# schemantic.net
KiCad netlist of a schematic drawn in EAGLE
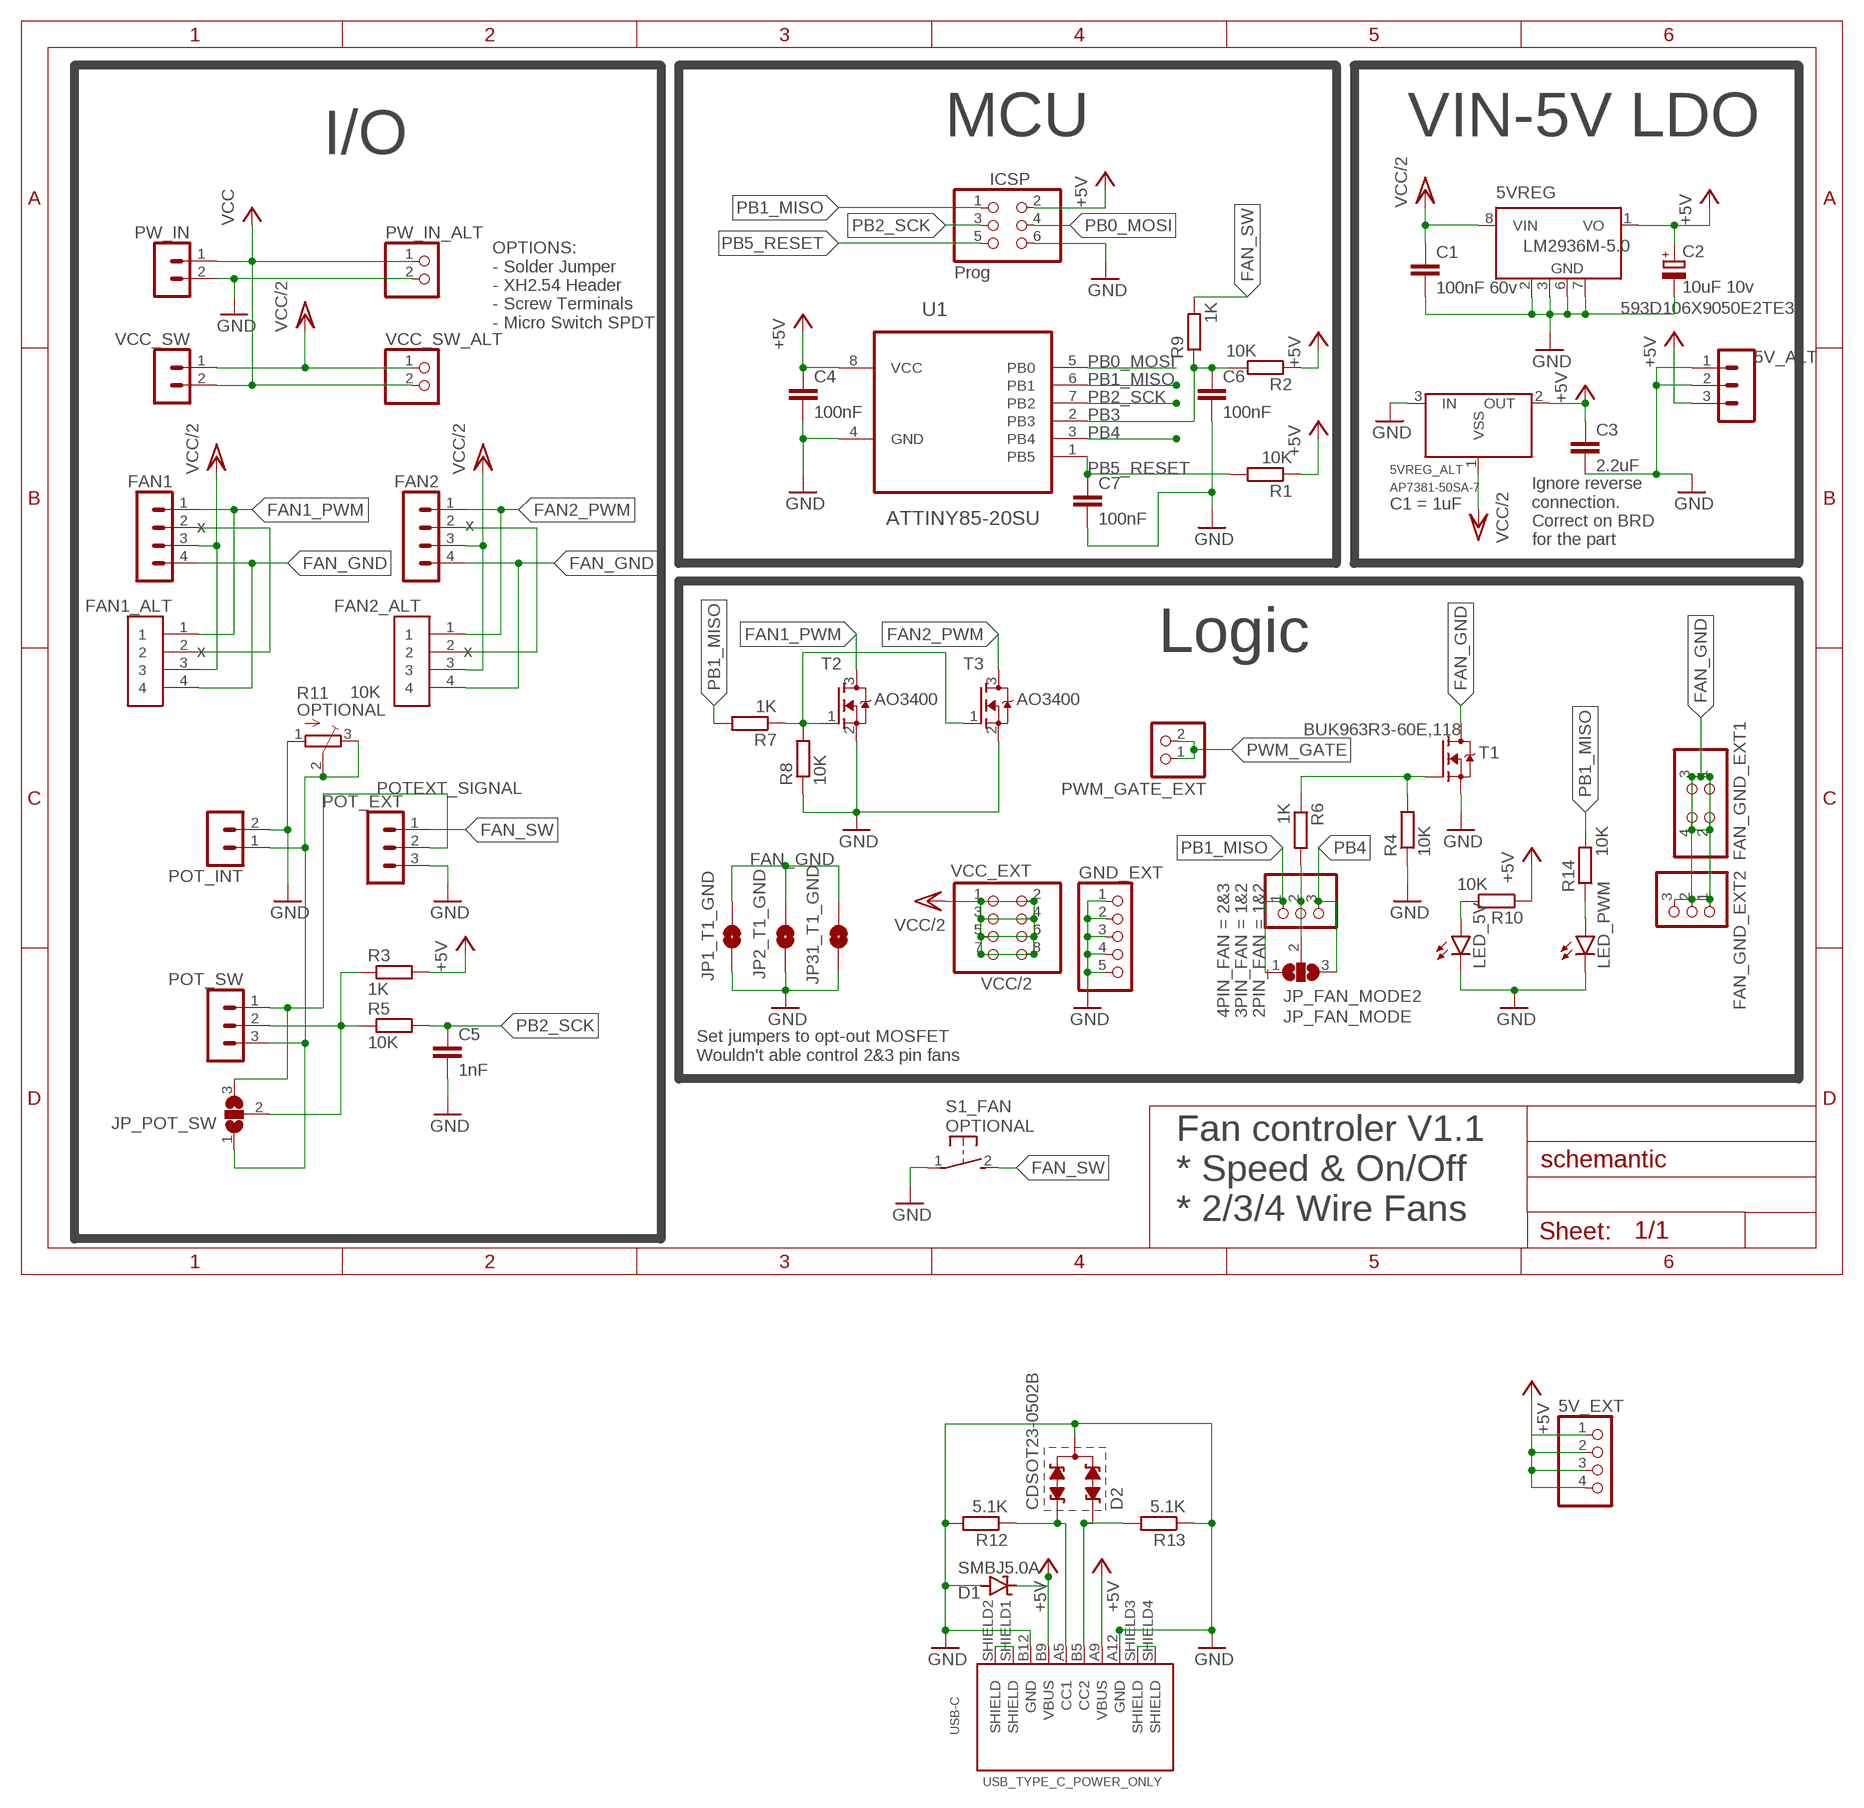
[diagram p0: schematic, sheet 1]

(export (version "E")
  (design (tool "Eeschema 10.0.6"))
  (components
    (comp (ref "5VREG")
      (value "LM2936M-5.0")
      (footprint "eagle-import:SO08")
      (fields
        (field (name "MF") "NATIONAL SEMICONDUCTOR")
        (field (name "MPN") "LM2936M-5.0/NOPB")
        (field (name "MPN_1") "LM2936HVMA-5.0/NOPB")
      )
      (libsource (lib "eagle-import") (part "LM2936M?-5.0"))
    )
    (comp (ref "5VREG_ALT")
      (value "AP7381-50SA-7")
      (footprint "eagle-import:XC6206_SOT-23")
      (fields (field (name "C1") "1uF"))
      (libsource (lib "eagle-import") (part "XC6206SOT-23"))
    )
    (comp (ref "5V_ALT")
      (value "B3B-XH-2")
      (footprint "eagle-import:B3B-XH-A")
      (libsource (lib "eagle-import") (part "B3B-XH-2"))
    )
    (comp (ref "5V_EXT")
      (value "PINHD-1X4")
      (footprint "eagle-import:1X04")
      (libsource (lib "eagle-import") (part "PINHD-1X4"))
    )
    (comp (ref "C1")
      (value "100nF 60v")
      (footprint "eagle-import:C1206")
      (libsource (lib "eagle-import") (part "C-EUC1206"))
    )
    (comp (ref "C2")
      (value "10uF 10v")
      (footprint "eagle-import:SMC_E")
      (fields (field (name "MODEL") "593D106X9050E2TE3"))
      (libsource (lib "eagle-import") (part "CPOL-EUSMCE"))
    )
    (comp (ref "C3")
      (value "2.2uF")
      (footprint "eagle-import:C0603")
      (libsource (lib "eagle-import") (part "C-EUC0603"))
    )
    (comp (ref "C4")
      (value "100nF")
      (footprint "eagle-import:C0603")
      (libsource (lib "eagle-import") (part "C-EUC0603"))
    )
    (comp (ref "C5")
      (value "1nF")
      (footprint "eagle-import:C0603")
      (libsource (lib "eagle-import") (part "C-EUC0603"))
    )
    (comp (ref "C6")
      (value "100nF")
      (footprint "eagle-import:C0603")
      (libsource (lib "eagle-import") (part "C-EUC0603"))
    )
    (comp (ref "C7")
      (value "100nF")
      (footprint "eagle-import:C0603")
      (libsource (lib "eagle-import") (part "C-EUC0603"))
    )
    (comp (ref "D1")
      (value "SMBJ5.0A")
      (footprint "eagle-import:SMBJ")
      (libsource (lib "eagle-import") (part "SUPPRESSOR-SMBJ"))
    )
    (comp (ref "D2")
      (value "CDSOT23-0502B")
      (footprint "eagle-import:SOT23")
      (libsource (lib "eagle-import") (part "CDSOT23-0502B"))
    )
    (comp (ref "FAN1")
      (value "FAN1")
      (footprint "eagle-import:B4P-VH")
      (libsource (lib "eagle-import") (part "B4P-VH"))
    )
    (comp (ref "FAN1_ALT")
      (value "1X4-BIG")
      (footprint "eagle-import:1X04-BIG")
      (libsource (lib "eagle-import") (part "1X4-BIG"))
    )
    (comp (ref "FAN2")
      (value "FAN1")
      (footprint "eagle-import:B4P-VH")
      (libsource (lib "eagle-import") (part "B4P-VH"))
    )
    (comp (ref "FAN2_ALT")
      (value "1X4-BIG")
      (footprint "eagle-import:1X04-BIG")
      (libsource (lib "eagle-import") (part "1X4-BIG"))
    )
    (comp (ref "FAN_GND_EXT1")
      (value "PINHD-2X2")
      (footprint "eagle-import:2X02")
      (libsource (lib "eagle-import") (part "PINHD-2X2"))
    )
    (comp (ref "FAN_GND_EXT2")
      (value "PINHD-1X3")
      (footprint "eagle-import:1X03")
      (libsource (lib "eagle-import") (part "pinhead_PINHD-1X3"))
    )
    (comp (ref "GND_EXT")
      (value "PINHD-1X5")
      (footprint "eagle-import:1X05")
      (libsource (lib "eagle-import") (part "PINHD-1X5"))
    )
    (comp (ref "ICSP")
      (value "Prog")
      (footprint "eagle-import:2X03")
      (libsource (lib "eagle-import") (part "PINHD-2X3"))
    )
    (comp (ref "JP1_T1_GND")
      (value "JUMPER-SMT_2_NO_NO-SILK")
      (footprint "eagle-import:SMT-JUMPER_2_NO_NO-SILK")
      (libsource (lib "eagle-import") (part "JUMPER-SMT_2_NO_NO-SILK"))
    )
    (comp (ref "JP2_T1_GND")
      (value "JUMPER-SMT_2_NO_NO-SILK")
      (footprint "eagle-import:SMT-JUMPER_2_NO_NO-SILK")
      (libsource (lib "eagle-import") (part "JUMPER-SMT_2_NO_NO-SILK"))
    )
    (comp (ref "JP31_T1_GND")
      (value "JUMPER-SMT_2_NO_NO-SILK")
      (footprint "eagle-import:SMT-JUMPER_2_NO_NO-SILK")
      (libsource (lib "eagle-import") (part "JUMPER-SMT_2_NO_NO-SILK"))
    )
    (comp (ref "JP_FAN_MODE")
      (value "DC_COM_PWM")
      (footprint "eagle-import:SJ_2")
      (libsource (lib "eagle-import") (part "SJ2W"))
    )
    (comp (ref "JP_FAN_MODE2")
      (value "PINHD-1X3")
      (footprint "eagle-import:1X03")
      (fields (field (name "2PIN_FAN") "1&2") (field (name "3PIN_FAN") "1&2") (field (name "4PIN_FAN") "2&3"))
      (libsource (lib "eagle-import") (part "PINHD-1X3"))
    )
    (comp (ref "JP_POT_SW")
      (value "SJ2W")
      (footprint "eagle-import:SJ_2")
      (libsource (lib "eagle-import") (part "SJ2W"))
    )
    (comp (ref "LED_5V")
      (value "LEDCHIPLED_0805")
      (footprint "eagle-import:CHIPLED_0805")
      (libsource (lib "eagle-import") (part "LEDCHIPLED_0805"))
    )
    (comp (ref "LED_PWM")
      (value "LEDCHIPLED_0805")
      (footprint "eagle-import:CHIPLED_0805")
      (libsource (lib "eagle-import") (part "LEDCHIPLED_0805"))
    )
    (comp (ref "POT_EXT")
      (value "POT_EXT")
      (footprint "eagle-import:B3B-XH-A")
      (libsource (lib "eagle-import") (part "B3B-XH-2"))
    )
    (comp (ref "POT_INT")
      (value "POT_INT")
      (footprint "eagle-import:B2B-XH-A")
      (libsource (lib "eagle-import") (part "B2B-XH-2"))
    )
    (comp (ref "POT_SW")
      (value "POT_SW")
      (footprint "eagle-import:B3B-XH-A")
      (libsource (lib "eagle-import") (part "B3B-XH-2"))
    )
    (comp (ref "PWM_GATE_EXT")
      (value "PINHD-1X2")
      (footprint "eagle-import:1X02")
      (libsource (lib "eagle-import") (part "PINHD-1X2"))
    )
    (comp (ref "PW_IN")
      (value "Power In")
      (footprint "eagle-import:B2P-VH")
      (libsource (lib "eagle-import") (part "B2P-VH"))
    )
    (comp (ref "PW_IN_ALT")
      (value "PINHD-1X2")
      (footprint "eagle-import:1X02")
      (libsource (lib "eagle-import") (part "pinhead_325_PINHD-1X2"))
    )
    (comp (ref "R1")
      (value "10K")
      (footprint "eagle-import:R0603")
      (fields (field (name "SPICEPREFIX") "R"))
      (libsource (lib "eagle-import") (part "R-EU_R0603"))
    )
    (comp (ref "R2")
      (value "10K")
      (footprint "eagle-import:R0603")
      (fields (field (name "SPICEPREFIX") "R"))
      (libsource (lib "eagle-import") (part "R-EU_R0603"))
    )
    (comp (ref "R3")
      (value "1K")
      (footprint "eagle-import:R0603")
      (libsource (lib "eagle-import") (part "R-EU_R0603"))
    )
    (comp (ref "R4")
      (value "10K")
      (footprint "eagle-import:R0603")
      (fields (field (name "SPICEPREFIX") "R"))
      (libsource (lib "eagle-import") (part "R-EU_R0603"))
    )
    (comp (ref "R5")
      (value "10K")
      (footprint "eagle-import:R0603")
      (libsource (lib "eagle-import") (part "R-EU_R0603"))
    )
    (comp (ref "R6")
      (value "1K")
      (footprint "eagle-import:R0603")
      (fields (field (name "SPICEPREFIX") "R"))
      (libsource (lib "eagle-import") (part "R-EU_R0603"))
    )
    (comp (ref "R7")
      (value "1K")
      (footprint "eagle-import:R0603")
      (fields (field (name "SPICEPREFIX") "R"))
      (libsource (lib "eagle-import") (part "R-EU_R0603"))
    )
    (comp (ref "R8")
      (value "10K")
      (footprint "eagle-import:R0603")
      (fields (field (name "SPICEPREFIX") "R"))
      (libsource (lib "eagle-import") (part "R-EU_R0603"))
    )
    (comp (ref "R9")
      (value "1K")
      (footprint "eagle-import:R0603")
      (libsource (lib "eagle-import") (part "R-EU_R0603"))
    )
    (comp (ref "R10")
      (value "10K")
      (footprint "eagle-import:R0603")
      (libsource (lib "eagle-import") (part "R-EU_R0603"))
    )
    (comp (ref "R11")
      (value "10K")
      (footprint "eagle-import:3223W")
      (libsource (lib "eagle-import") (part "TRIM_EU-3223W"))
    )
    (comp (ref "R12")
      (value "5.1K")
      (footprint "eagle-import:R0603")
      (libsource (lib "eagle-import") (part "R-EU_R0603"))
    )
    (comp (ref "R13")
      (value "5.1K")
      (footprint "eagle-import:R0603")
      (libsource (lib "eagle-import") (part "R-EU_R0603"))
    )
    (comp (ref "R14")
      (value "10K")
      (footprint "eagle-import:R0603")
      (libsource (lib "eagle-import") (part "R-EU_R0603"))
    )
    (comp (ref "S1_FAN")
      (value "DTSM-3")
      (footprint "eagle-import:DTSM-3")
      (libsource (lib "eagle-import") (part "DTSM-3"))
    )
    (comp (ref "T1")
      (value "BUK963R3-60E,118")
      (footprint "eagle-import:D2PAK_TO263")
      (libsource (lib "eagle-import") (part "MOSFET-N-D2PAK"))
    )
    (comp (ref "T2")
      (value "AO3400")
      (footprint "eagle-import:SOT23")
      (fields (field (name "SPICEPREFIX") "J"))
      (libsource (lib "eagle-import") (part "MOSFET-NREFLOW"))
    )
    (comp (ref "T3")
      (value "AO3400")
      (footprint "eagle-import:SOT23")
      (fields (field (name "SPICEPREFIX") "J"))
      (libsource (lib "eagle-import") (part "MOSFET-NREFLOW"))
    )
    (comp (ref "U1")
      (value "ATTINY85-20SU")
      (footprint "eagle-import:SOIC127P798X216-8N")
      (libsource (lib "eagle-import") (part "ATTINY85-20SU"))
    )
    (comp (ref "USB-C")
      (value "USB_TYPE_C_POWER_ONLY")
      (footprint "eagle-import:USB_TYPE_C_POWER_ONLY")
      (libsource (lib "eagle-import") (part "USB_TYPE_C_POWER_ONLY"))
    )
    (comp (ref "VCC_EXT")
      (value "PINHD-2X4")
      (footprint "eagle-import:2X04")
      (libsource (lib "eagle-import") (part "PINHD-2X4"))
    )
    (comp (ref "VCC_SW")
      (value "Power SW")
      (footprint "eagle-import:B2P-VH")
      (libsource (lib "eagle-import") (part "B2P-VH"))
    )
    (comp (ref "VCC_SW_ALT")
      (value "PINHD-1X2")
      (footprint "eagle-import:1X02")
      (libsource (lib "eagle-import") (part "pinhead_325_PINHD-1X2"))
    )
  )
  (nets
    (net (code "1") (name "+5V") (class "Default")
      (node (ref "5VREG") (pin "1") (pinfunction "VO_1") (pintype "passive"))
      (node (ref "5VREG_ALT") (pin "2") (pinfunction "OUT_2") (pintype "bidirectional"))
      (node (ref "5V_ALT") (pin "3") (pinfunction "3_3") (pintype "passive"))
      (node (ref "5V_EXT") (pin "1") (pinfunction "1_1") (pintype "passive"))
      (node (ref "5V_EXT") (pin "2") (pinfunction "2_2") (pintype "passive"))
      (node (ref "5V_EXT") (pin "3") (pinfunction "3_3") (pintype "passive"))
      (node (ref "5V_EXT") (pin "4") (pinfunction "4_4") (pintype "passive"))
      (node (ref "C2") (pin "+") (pinfunction "+_+") (pintype "passive"))
      (node (ref "C3") (pin "1") (pinfunction "1_1") (pintype "passive"))
      (node (ref "C4") (pin "1") (pinfunction "1_1") (pintype "passive"))
      (node (ref "D1") (pin "C") (pinfunction "C_C") (pintype "passive"))
      (node (ref "ICSP") (pin "2") (pinfunction "2_2") (pintype "passive"))
      (node (ref "R1") (pin "1") (pinfunction "1_1") (pintype "passive"))
      (node (ref "R10") (pin "1") (pinfunction "1_1") (pintype "passive"))
      (node (ref "R2") (pin "1") (pinfunction "1_1") (pintype "passive"))
      (node (ref "R3") (pin "2") (pinfunction "2_2") (pintype "passive"))
      (node (ref "U1") (pin "8") (pinfunction "VCC_8") (pintype "power_in"))
      (node (ref "USB-C") (pin "A9") (pinfunction "VBUS_A9") (pintype "power_in"))
      (node (ref "USB-C") (pin "B9") (pinfunction "VBUS_B9") (pintype "power_in"))
    )
    (net (code "2") (name "/PB3") (class "Default")
      (node (ref "C6") (pin "1") (pinfunction "1_1") (pintype "passive"))
      (node (ref "R2") (pin "2") (pinfunction "2_2") (pintype "passive"))
      (node (ref "R9") (pin "1") (pinfunction "1_1") (pintype "passive"))
      (node (ref "U1") (pin "2") (pinfunction "PB3_2") (pintype "bidirectional"))
    )
    (net (code "3") (name "/POTEXT_SIGNAL") (class "Default")
      (node (ref "JP_POT_SW") (pin "3") (pinfunction "3_3") (pintype "passive"))
      (node (ref "POT_EXT") (pin "2") (pinfunction "2_2") (pintype "passive"))
      (node (ref "POT_SW") (pin "1") (pinfunction "1_1") (pintype "passive"))
    )
    (net (code "4") (name "FAN1_PWM") (class "Default")
      (node (ref "FAN1") (pin "1") (pinfunction "1_1") (pintype "passive"))
      (node (ref "FAN1_ALT") (pin "1") (pinfunction "1_1") (pintype "bidirectional"))
      (node (ref "T2") (pin "3") (pinfunction "D_3") (pintype "bidirectional"))
    )
    (net (code "5") (name "FAN2_PWM") (class "Default")
      (node (ref "FAN2") (pin "1") (pinfunction "1_1") (pintype "passive"))
      (node (ref "FAN2_ALT") (pin "1") (pinfunction "1_1") (pintype "bidirectional"))
      (node (ref "T3") (pin "3") (pinfunction "D_3") (pintype "bidirectional"))
    )
    (net (code "6") (name "FAN_GND") (class "Default")
      (node (ref "FAN1") (pin "4") (pinfunction "4_4") (pintype "passive"))
      (node (ref "FAN1_ALT") (pin "4") (pinfunction "4_4") (pintype "bidirectional"))
      (node (ref "FAN2") (pin "4") (pinfunction "4_4") (pintype "passive"))
      (node (ref "FAN2_ALT") (pin "4") (pinfunction "4_4") (pintype "bidirectional"))
      (node (ref "FAN_GND_EXT1") (pin "1") (pinfunction "1_1") (pintype "passive"))
      (node (ref "FAN_GND_EXT1") (pin "2") (pinfunction "2_2") (pintype "passive"))
      (node (ref "FAN_GND_EXT1") (pin "3") (pinfunction "3_3") (pintype "passive"))
      (node (ref "FAN_GND_EXT1") (pin "4") (pinfunction "4_4") (pintype "passive"))
      (node (ref "FAN_GND_EXT2") (pin "1") (pinfunction "1_1") (pintype "passive"))
      (node (ref "FAN_GND_EXT2") (pin "2") (pinfunction "2_2") (pintype "passive"))
      (node (ref "FAN_GND_EXT2") (pin "3") (pinfunction "3_3") (pintype "passive"))
      (node (ref "JP1_T1_GND") (pin "2") (pinfunction "2_2") (pintype "passive"))
      (node (ref "JP2_T1_GND") (pin "2") (pinfunction "2_2") (pintype "passive"))
      (node (ref "JP31_T1_GND") (pin "2") (pinfunction "2_2") (pintype "passive"))
      (node (ref "T1") (pin "2") (pinfunction "D_2") (pintype "passive"))
    )
    (net (code "7") (name "FAN_SW") (class "Default")
      (node (ref "POT_EXT") (pin "1") (pinfunction "1_1") (pintype "passive"))
      (node (ref "R9") (pin "2") (pinfunction "2_2") (pintype "passive"))
      (node (ref "S1_FAN") (pin "2") (pinfunction "2_2") (pintype "passive"))
    )
    (net (code "8") (name "GND") (class "Default")
      (node (ref "5VREG") (pin "2") (pinfunction "GND_2") (pintype "passive"))
      (node (ref "5VREG") (pin "3") (pinfunction "GND_3") (pintype "passive"))
      (node (ref "5VREG") (pin "6") (pinfunction "GND_6") (pintype "passive"))
      (node (ref "5VREG") (pin "7") (pinfunction "GND_7") (pintype "passive"))
      (node (ref "5VREG_ALT") (pin "3") (pinfunction "IN_3") (pintype "bidirectional"))
      (node (ref "5V_ALT") (pin "1") (pinfunction "1_1") (pintype "passive"))
      (node (ref "5V_ALT") (pin "2") (pinfunction "2_2") (pintype "passive"))
      (node (ref "C1") (pin "2") (pinfunction "2_2") (pintype "passive"))
      (node (ref "C2") (pin "-") (pinfunction "-_-") (pintype "passive"))
      (node (ref "C3") (pin "2") (pinfunction "2_2") (pintype "passive"))
      (node (ref "C4") (pin "2") (pinfunction "2_2") (pintype "passive"))
      (node (ref "C5") (pin "2") (pinfunction "2_2") (pintype "passive"))
      (node (ref "C6") (pin "2") (pinfunction "2_2") (pintype "passive"))
      (node (ref "C7") (pin "2") (pinfunction "2_2") (pintype "passive"))
      (node (ref "D1") (pin "A") (pinfunction "A_A") (pintype "passive"))
      (node (ref "D2") (pin "3") (pinfunction "3_3") (pintype "passive"))
      (node (ref "GND_EXT") (pin "1") (pinfunction "1_1") (pintype "passive"))
      (node (ref "GND_EXT") (pin "2") (pinfunction "2_2") (pintype "passive"))
      (node (ref "GND_EXT") (pin "3") (pinfunction "3_3") (pintype "passive"))
      (node (ref "GND_EXT") (pin "4") (pinfunction "4_4") (pintype "passive"))
      (node (ref "GND_EXT") (pin "5") (pinfunction "5_5") (pintype "passive"))
      (node (ref "ICSP") (pin "6") (pinfunction "6_6") (pintype "passive"))
      (node (ref "JP1_T1_GND") (pin "1") (pinfunction "1_1") (pintype "passive"))
      (node (ref "JP2_T1_GND") (pin "1") (pinfunction "1_1") (pintype "passive"))
      (node (ref "JP31_T1_GND") (pin "1") (pinfunction "1_1") (pintype "passive"))
      (node (ref "LED_5V") (pin "C") (pinfunction "C_C") (pintype "passive"))
      (node (ref "LED_PWM") (pin "C") (pinfunction "C_C") (pintype "passive"))
      (node (ref "POT_EXT") (pin "3") (pinfunction "3_3") (pintype "passive"))
      (node (ref "POT_INT") (pin "2") (pinfunction "2_2") (pintype "passive"))
      (node (ref "PW_IN") (pin "2") (pinfunction "2_2") (pintype "passive"))
      (node (ref "PW_IN_ALT") (pin "2") (pinfunction "2_2") (pintype "passive"))
      (node (ref "R11") (pin "1") (pinfunction "A_1") (pintype "passive"))
      (node (ref "R12") (pin "2") (pinfunction "2_2") (pintype "passive"))
      (node (ref "R13") (pin "1") (pinfunction "1_1") (pintype "passive"))
      (node (ref "R4") (pin "1") (pinfunction "1_1") (pintype "passive"))
      (node (ref "R8") (pin "1") (pinfunction "1_1") (pintype "passive"))
      (node (ref "S1_FAN") (pin "1") (pinfunction "1_1") (pintype "passive"))
      (node (ref "T1") (pin "3") (pinfunction "S_3") (pintype "passive"))
      (node (ref "T2") (pin "2") (pinfunction "S_2") (pintype "bidirectional"))
      (node (ref "T3") (pin "2") (pinfunction "S_2") (pintype "bidirectional"))
      (node (ref "U1") (pin "4") (pinfunction "GND_4") (pintype "passive"))
      (node (ref "USB-C") (pin "A12") (pinfunction "GND_A12") (pintype "power_in"))
      (node (ref "USB-C") (pin "B12") (pinfunction "GND_B12") (pintype "power_in"))
    )
    (net (code "9") (name "Net-(FAN1-Pad2)") (class "Default")
      (node (ref "FAN1") (pin "2") (pinfunction "2_2") (pintype "passive"))
      (node (ref "FAN1_ALT") (pin "2") (pinfunction "2_2") (pintype "bidirectional"))
    )
    (net (code "10") (name "Net-(FAN2-Pad2)") (class "Default")
      (node (ref "FAN2") (pin "2") (pinfunction "2_2") (pintype "passive"))
      (node (ref "FAN2_ALT") (pin "2") (pinfunction "2_2") (pintype "bidirectional"))
    )
    (net (code "11") (name "Net-(JP_FAN_MODE-Pad2)") (class "Default")
      (node (ref "JP_FAN_MODE") (pin "2") (pinfunction "2_2") (pintype "passive"))
      (node (ref "JP_FAN_MODE2") (pin "2") (pinfunction "2_2") (pintype "passive"))
      (node (ref "R6") (pin "2") (pinfunction "2_2") (pintype "passive"))
    )
    (net (code "12") (name "Net-(JP_POT_SW-Pad2)") (class "Default")
      (node (ref "JP_POT_SW") (pin "2") (pinfunction "2_2") (pintype "passive"))
      (node (ref "POT_SW") (pin "2") (pinfunction "2_2") (pintype "passive"))
      (node (ref "R3") (pin "1") (pinfunction "1_1") (pintype "passive"))
      (node (ref "R5") (pin "1") (pinfunction "1_1") (pintype "passive"))
    )
    (net (code "13") (name "Net-(LED_5V-PadA)") (class "Default")
      (node (ref "LED_5V") (pin "A") (pinfunction "A_A") (pintype "passive"))
      (node (ref "R10") (pin "2") (pinfunction "2_2") (pintype "passive"))
    )
    (net (code "14") (name "Net-(LED_PWM-PadA)") (class "Default")
      (node (ref "LED_PWM") (pin "A") (pinfunction "A_A") (pintype "passive"))
      (node (ref "R14") (pin "1") (pinfunction "1_1") (pintype "passive"))
    )
    (net (code "15") (name "Net-(R11-E)") (class "Default")
      (node (ref "JP_POT_SW") (pin "1") (pinfunction "1_1") (pintype "passive"))
      (node (ref "POT_INT") (pin "1") (pinfunction "1_1") (pintype "passive"))
      (node (ref "POT_SW") (pin "3") (pinfunction "3_3") (pintype "passive"))
      (node (ref "R11") (pin "2") (pinfunction "S_2") (pintype "passive"))
      (node (ref "R11") (pin "3") (pinfunction "E_3") (pintype "passive"))
    )
    (net (code "16") (name "Net-(T1-G)") (class "Default")
      (node (ref "R4") (pin "2") (pinfunction "2_2") (pintype "passive"))
      (node (ref "R6") (pin "1") (pinfunction "1_1") (pintype "passive"))
      (node (ref "T1") (pin "1") (pinfunction "G_1") (pintype "passive"))
    )
    (net (code "17") (name "Net-(USB-C-CC1)") (class "Default")
      (node (ref "D2") (pin "2") (pinfunction "2_2") (pintype "passive"))
      (node (ref "R12") (pin "1") (pinfunction "1_1") (pintype "passive"))
      (node (ref "USB-C") (pin "A5") (pinfunction "CC1_A5") (pintype "bidirectional"))
    )
    (net (code "18") (name "Net-(USB-C-CC2)") (class "Default")
      (node (ref "D2") (pin "1") (pinfunction "1_1") (pintype "passive"))
      (node (ref "R13") (pin "2") (pinfunction "2_2") (pintype "passive"))
      (node (ref "USB-C") (pin "B5") (pinfunction "CC2_B5") (pintype "bidirectional"))
    )
    (net (code "19") (name "Net-(USB-C-SHIELD-PadSHIELD1)") (class "Default")
      (node (ref "USB-C") (pin "SHIELD1") (pinfunction "SHIELD_SHIELD1") (pintype "power_in"))
      (node (ref "USB-C") (pin "SHIELD2") (pinfunction "SHIELD_SHIELD2") (pintype "power_in"))
    )
    (net (code "20") (name "Net-(USB-C-SHIELD-PadSHIELD3)") (class "Default")
      (node (ref "USB-C") (pin "SHIELD3") (pinfunction "SHIELD_SHIELD3") (pintype "power_in"))
      (node (ref "USB-C") (pin "SHIELD4") (pinfunction "SHIELD_SHIELD4") (pintype "power_in"))
    )
    (net (code "21") (name "PB0_MOSI") (class "Default")
      (node (ref "ICSP") (pin "4") (pinfunction "4_4") (pintype "passive"))
      (node (ref "U1") (pin "5") (pinfunction "PB0_5") (pintype "bidirectional"))
    )
    (net (code "22") (name "PB1_MISO") (class "Default")
      (node (ref "ICSP") (pin "1") (pinfunction "1_1") (pintype "passive"))
      (node (ref "JP_FAN_MODE") (pin "1") (pinfunction "1_1") (pintype "passive"))
      (node (ref "JP_FAN_MODE2") (pin "1") (pinfunction "1_1") (pintype "passive"))
      (node (ref "R14") (pin "2") (pinfunction "2_2") (pintype "passive"))
      (node (ref "R7") (pin "2") (pinfunction "2_2") (pintype "passive"))
      (node (ref "U1") (pin "6") (pinfunction "PB1_6") (pintype "bidirectional"))
    )
    (net (code "23") (name "PB2_SCK") (class "Default")
      (node (ref "C5") (pin "1") (pinfunction "1_1") (pintype "passive"))
      (node (ref "ICSP") (pin "3") (pinfunction "3_3") (pintype "passive"))
      (node (ref "R5") (pin "2") (pinfunction "2_2") (pintype "passive"))
      (node (ref "U1") (pin "7") (pinfunction "PB2_7") (pintype "bidirectional"))
    )
    (net (code "24") (name "PB4") (class "Default")
      (node (ref "JP_FAN_MODE") (pin "3") (pinfunction "3_3") (pintype "passive"))
      (node (ref "JP_FAN_MODE2") (pin "3") (pinfunction "3_3") (pintype "passive"))
      (node (ref "U1") (pin "3") (pinfunction "PB4_3") (pintype "bidirectional"))
    )
    (net (code "25") (name "PB5_RESET") (class "Default")
      (node (ref "C7") (pin "1") (pinfunction "1_1") (pintype "passive"))
      (node (ref "ICSP") (pin "5") (pinfunction "5_5") (pintype "passive"))
      (node (ref "R1") (pin "2") (pinfunction "2_2") (pintype "passive"))
      (node (ref "U1") (pin "1") (pinfunction "PB5_1") (pintype "bidirectional"))
    )
    (net (code "26") (name "PWM_GATE") (class "Default")
      (node (ref "PWM_GATE_EXT") (pin "1") (pinfunction "1_1") (pintype "passive"))
      (node (ref "PWM_GATE_EXT") (pin "2") (pinfunction "2_2") (pintype "passive"))
      (node (ref "R7") (pin "1") (pinfunction "1_1") (pintype "passive"))
      (node (ref "R8") (pin "2") (pinfunction "2_2") (pintype "passive"))
      (node (ref "T2") (pin "1") (pinfunction "G_1") (pintype "bidirectional"))
      (node (ref "T3") (pin "1") (pinfunction "G_1") (pintype "bidirectional"))
    )
    (net (code "27") (name "VCC") (class "Default")
      (node (ref "PW_IN") (pin "1") (pinfunction "1_1") (pintype "passive"))
      (node (ref "PW_IN_ALT") (pin "1") (pinfunction "1_1") (pintype "passive"))
      (node (ref "VCC_SW") (pin "2") (pinfunction "2_2") (pintype "passive"))
      (node (ref "VCC_SW_ALT") (pin "2") (pinfunction "2_2") (pintype "passive"))
    )
    (net (code "28") (name "VCC{slash}2") (class "Default")
      (node (ref "5VREG") (pin "8") (pinfunction "VIN_8") (pintype "input"))
      (node (ref "5VREG_ALT") (pin "1") (pinfunction "VSS_1") (pintype "bidirectional"))
      (node (ref "C1") (pin "1") (pinfunction "1_1") (pintype "passive"))
      (node (ref "FAN1") (pin "3") (pinfunction "3_3") (pintype "passive"))
      (node (ref "FAN1_ALT") (pin "3") (pinfunction "3_3") (pintype "bidirectional"))
      (node (ref "FAN2") (pin "3") (pinfunction "3_3") (pintype "passive"))
      (node (ref "FAN2_ALT") (pin "3") (pinfunction "3_3") (pintype "bidirectional"))
      (node (ref "VCC_EXT") (pin "1") (pinfunction "1_1") (pintype "passive"))
      (node (ref "VCC_EXT") (pin "2") (pinfunction "2_2") (pintype "passive"))
      (node (ref "VCC_EXT") (pin "3") (pinfunction "3_3") (pintype "passive"))
      (node (ref "VCC_EXT") (pin "4") (pinfunction "4_4") (pintype "passive"))
      (node (ref "VCC_EXT") (pin "5") (pinfunction "5_5") (pintype "passive"))
      (node (ref "VCC_EXT") (pin "6") (pinfunction "6_6") (pintype "passive"))
      (node (ref "VCC_EXT") (pin "7") (pinfunction "7_7") (pintype "passive"))
      (node (ref "VCC_EXT") (pin "8") (pinfunction "8_8") (pintype "passive"))
      (node (ref "VCC_SW") (pin "1") (pinfunction "1_1") (pintype "passive"))
      (node (ref "VCC_SW_ALT") (pin "1") (pinfunction "1_1") (pintype "passive"))
    )
  )
)
